# avr_programming_shield_Zif-Ken_reduced_b.net
KiCad netlist of a schematic drawn in EAGLE
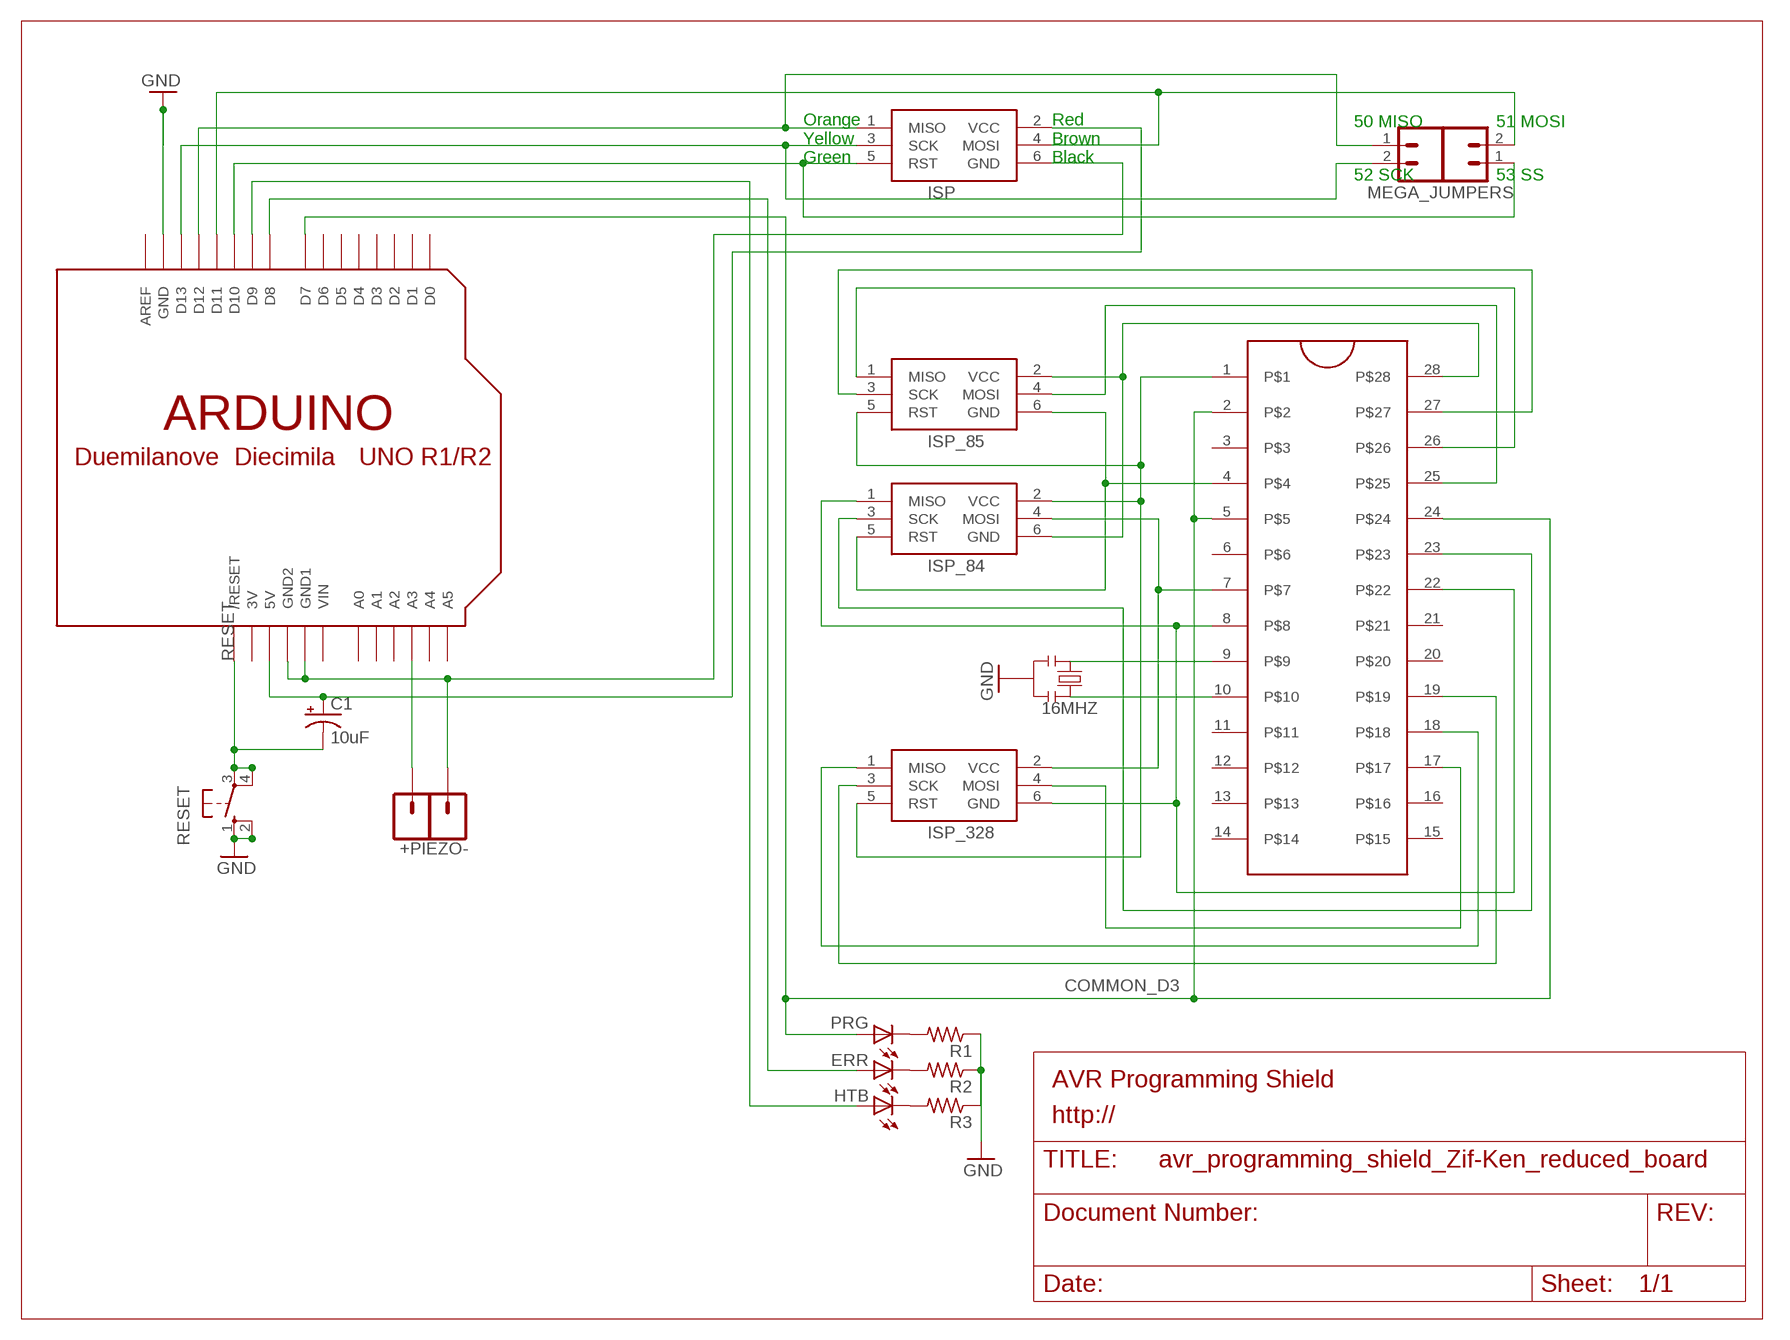
[diagram p0: schematic, sheet 1]

(export (version "E")
  (design (tool "Eeschema 10.0.6"))
  (components
    (comp (ref "+PIEZO-")
      (value "M01PTH")
      (footprint "eagle-import:1X01")
      (libsource (lib "eagle-import") (part "M01PTH"))
    )
    (comp (ref "16MHZ")
      (value "RESONATORPTH")
      (footprint "eagle-import:RESONATOR-PTH")
      (libsource (lib "eagle-import") (part "RESONATORPTH"))
    )
    (comp (ref "C1")
      (value "10uF")
      (footprint "eagle-import:CPOL-RADIAL-10UF-25V")
      (libsource (lib "eagle-import") (part "CAP_POLPTH2"))
    )
    (comp (ref "ERR")
      (value "LED3MM")
      (footprint "eagle-import:LED3MM")
      (libsource (lib "eagle-import") (part "LED3MM"))
    )
    (comp (ref "HTB")
      (value "LED3MM")
      (footprint "eagle-import:LED3MM")
      (libsource (lib "eagle-import") (part "LED3MM"))
    )
    (comp (ref "ISP")
      (value "AVRISP-6")
      (footprint "eagle-import:AVRISP")
      (libsource (lib "eagle-import") (part "AVRISP-6"))
    )
    (comp (ref "ISP_84")
      (value "AVRISP-6")
      (footprint "eagle-import:AVRISP")
      (libsource (lib "eagle-import") (part "AVRISP-6"))
    )
    (comp (ref "ISP_85")
      (value "AVRISP-6")
      (footprint "eagle-import:AVRISP")
      (libsource (lib "eagle-import") (part "AVRISP-6"))
    )
    (comp (ref "ISP_328")
      (value "AVRISP-6")
      (footprint "eagle-import:AVRISP")
      (libsource (lib "eagle-import") (part "AVRISP-6"))
    )
    (comp (ref "JP2")
      (value "M02PTH")
      (footprint "eagle-import:1X02")
      (libsource (lib "eagle-import") (part "M02PTH"))
    )
    (comp (ref "JP4")
      (value "M01PTH")
      (footprint "eagle-import:1X01")
      (libsource (lib "eagle-import") (part "M01PTH"))
    )
    (comp (ref "MEGA_JUMPERS")
      (value "M02PTH")
      (footprint "eagle-import:1X02")
      (libsource (lib "eagle-import") (part "M02PTH"))
    )
    (comp (ref "PRG")
      (value "LED3MM")
      (footprint "eagle-import:LED3MM")
      (libsource (lib "eagle-import") (part "LED3MM"))
    )
    (comp (ref "R1")
      (value "R-US_0204/2V")
      (footprint "eagle-import:0204V")
      (libsource (lib "eagle-import") (part "R-US_0204/2V"))
    )
    (comp (ref "R2")
      (value "R-US_0204/2V")
      (footprint "eagle-import:0204V")
      (libsource (lib "eagle-import") (part "R-US_0204/2V"))
    )
    (comp (ref "R3")
      (value "R-US_0204/2V")
      (footprint "eagle-import:0204V")
      (libsource (lib "eagle-import") (part "R-US_0204/2V"))
    )
    (comp (ref "RESET")
      (value "10-XX")
      (footprint "eagle-import:B3F-10XX")
      (fields (field (name "MPN") "B3F-1000"))
      (libsource (lib "eagle-import") (part "10-XX"))
    )
    (comp (ref "U$1")
      (value "ARDUINO-NOHOLE")
      (footprint "eagle-import:ARDUINO-NOHOLE")
      (libsource (lib "eagle-import") (part "ARDUINO-NOHOLE"))
    )
    (comp (ref "U$4")
      (value "ZIFSOCKET-28-3ZIFFSOCKET-28-3")
      (footprint "eagle-import:DIL28-3-ZIF_SOCKET")
      (libsource (lib "eagle-import") (part "ZIFSOCKET-28-3ZIFFSOCKET-28-3"))
    )
  )
  (nets
    (net (code "1") (name "/3V") (class "Default")
      (node (ref "U$1") (pin "3V") (pinfunction "3V_3V") (pintype "power_in"))
    )
    (net (code "2") (name "/COMMON_D3") (class "Default")
      (node (ref "PRG") (pin "A") (pinfunction "A_A") (pintype "passive"))
      (node (ref "U$1") (pin "D7") (pinfunction "D7_D7") (pintype "bidirectional"))
      (node (ref "U$4") (pin "2") (pinfunction "P$2_2") (pintype "bidirectional"))
      (node (ref "U$4") (pin "24") (pinfunction "P$24_24") (pintype "bidirectional"))
      (node (ref "U$4") (pin "5") (pinfunction "P$5_5") (pintype "bidirectional"))
    )
    (net (code "3") (name "/RESET") (class "Default")
      (node (ref "C1") (pin "2") (pinfunction "-_2") (pintype "passive"))
      (node (ref "RESET") (pin "3") (pinfunction "P_3") (pintype "passive"))
      (node (ref "RESET") (pin "4") (pinfunction "P1_4") (pintype "passive"))
      (node (ref "U$1") (pin "RESET") (pinfunction "/RESET_RESET") (pintype "bidirectional"))
    )
    (net (code "4") (name "/VIN") (class "Default")
      (node (ref "U$1") (pin "VIN") (pinfunction "VIN_VIN") (pintype "power_in"))
    )
    (net (code "5") (name "GND") (class "Default")
      (node (ref "+PIEZO-") (pin "1") (pinfunction "1_1") (pintype "passive"))
      (node (ref "16MHZ") (pin "2") (pinfunction "2_2") (pintype "passive"))
      (node (ref "ISP") (pin "6") (pinfunction "GND_6") (pintype "power_in"))
      (node (ref "R1") (pin "1") (pinfunction "1_1") (pintype "passive"))
      (node (ref "R2") (pin "1") (pinfunction "1_1") (pintype "passive"))
      (node (ref "R3") (pin "1") (pinfunction "1_1") (pintype "passive"))
      (node (ref "RESET") (pin "1") (pinfunction "S_1") (pintype "passive"))
      (node (ref "RESET") (pin "2") (pinfunction "S1_2") (pintype "passive"))
      (node (ref "U$1") (pin "GND") (pinfunction "GND_GND") (pintype "power_in"))
      (node (ref "U$1") (pin "GND1") (pinfunction "GND1_GND1") (pintype "power_in"))
      (node (ref "U$1") (pin "GND2") (pinfunction "GND2_GND2") (pintype "power_in"))
    )
    (net (code "6") (name "Net-(C1-+)") (class "Default")
      (node (ref "C1") (pin "1") (pinfunction "+_1") (pintype "passive"))
      (node (ref "ISP") (pin "2") (pinfunction "VCC_2") (pintype "power_in"))
      (node (ref "U$1") (pin "5V") (pinfunction "5V_5V") (pintype "power_in"))
    )
    (net (code "7") (name "Net-(ERR-C)") (class "Default")
      (node (ref "ERR") (pin "K") (pinfunction "C_K") (pintype "passive"))
      (node (ref "R2") (pin "2") (pinfunction "2_2") (pintype "passive"))
    )
    (net (code "8") (name "Net-(ERR-PadA)") (class "Default")
      (node (ref "ERR") (pin "A") (pinfunction "A_A") (pintype "passive"))
      (node (ref "U$1") (pin "D8") (pinfunction "D8_D8") (pintype "bidirectional"))
    )
    (net (code "9") (name "Net-(HTB-C)") (class "Default")
      (node (ref "HTB") (pin "K") (pinfunction "C_K") (pintype "passive"))
      (node (ref "R3") (pin "2") (pinfunction "2_2") (pintype "passive"))
    )
    (net (code "10") (name "Net-(HTB-PadA)") (class "Default")
      (node (ref "HTB") (pin "A") (pinfunction "A_A") (pintype "passive"))
      (node (ref "U$1") (pin "D9") (pinfunction "D9_D9") (pintype "bidirectional"))
    )
    (net (code "11") (name "Net-(ISP-MISO)") (class "Default")
      (node (ref "ISP") (pin "1") (pinfunction "MISO_1") (pintype "input"))
      (node (ref "MEGA_JUMPERS") (pin "1") (pinfunction "1_1") (pintype "passive"))
      (node (ref "U$1") (pin "D12") (pinfunction "D12_D12") (pintype "bidirectional"))
    )
    (net (code "12") (name "Net-(ISP-MOSI)") (class "Default")
      (node (ref "ISP") (pin "4") (pinfunction "MOSI_4") (pintype "output"))
      (node (ref "JP2") (pin "2") (pinfunction "2_2") (pintype "passive"))
      (node (ref "U$1") (pin "D11") (pinfunction "D11_D11") (pintype "bidirectional"))
    )
    (net (code "13") (name "Net-(ISP-RST)") (class "Default")
      (node (ref "ISP") (pin "5") (pinfunction "RST_5") (pintype "output"))
      (node (ref "JP2") (pin "1") (pinfunction "1_1") (pintype "passive"))
      (node (ref "U$1") (pin "D10") (pinfunction "D10_D10") (pintype "bidirectional"))
    )
    (net (code "14") (name "Net-(ISP-SCK)") (class "Default")
      (node (ref "ISP") (pin "3") (pinfunction "SCK_3") (pintype "output"))
      (node (ref "MEGA_JUMPERS") (pin "2") (pinfunction "2_2") (pintype "passive"))
      (node (ref "U$1") (pin "D13") (pinfunction "D13_D13") (pintype "bidirectional"))
    )
    (net (code "15") (name "Net-(ISP_84-GND)") (class "Default")
      (node (ref "ISP_84") (pin "6") (pinfunction "GND_6") (pintype "power_in"))
      (node (ref "ISP_85") (pin "2") (pinfunction "VCC_2") (pintype "power_in"))
      (node (ref "U$4") (pin "28") (pinfunction "P$28_28") (pintype "bidirectional"))
    )
    (net (code "16") (name "Net-(ISP_84-RST)") (class "Default")
      (node (ref "ISP_84") (pin "5") (pinfunction "RST_5") (pintype "output"))
      (node (ref "ISP_85") (pin "6") (pinfunction "GND_6") (pintype "power_in"))
      (node (ref "U$4") (pin "4") (pinfunction "P$4_4") (pintype "bidirectional"))
    )
    (net (code "17") (name "Net-(ISP_84-SCK)") (class "Default")
      (node (ref "ISP_84") (pin "3") (pinfunction "SCK_3") (pintype "output"))
      (node (ref "U$4") (pin "23") (pinfunction "P$23_23") (pintype "bidirectional"))
    )
    (net (code "18") (name "Net-(ISP_85-MISO)") (class "Default")
      (node (ref "ISP_85") (pin "1") (pinfunction "MISO_1") (pintype "input"))
      (node (ref "U$4") (pin "26") (pinfunction "P$26_26") (pintype "bidirectional"))
    )
    (net (code "19") (name "Net-(ISP_85-MOSI)") (class "Default")
      (node (ref "ISP_85") (pin "4") (pinfunction "MOSI_4") (pintype "output"))
      (node (ref "U$4") (pin "25") (pinfunction "P$25_25") (pintype "bidirectional"))
    )
    (net (code "20") (name "Net-(ISP_85-SCK)") (class "Default")
      (node (ref "ISP_85") (pin "3") (pinfunction "SCK_3") (pintype "output"))
      (node (ref "U$4") (pin "27") (pinfunction "P$27_27") (pintype "bidirectional"))
    )
    (net (code "21") (name "Net-(ISP_328-GND)") (class "Default")
      (node (ref "ISP_328") (pin "6") (pinfunction "GND_6") (pintype "power_in"))
      (node (ref "ISP_84") (pin "1") (pinfunction "MISO_1") (pintype "input"))
      (node (ref "U$4") (pin "22") (pinfunction "P$22_22") (pintype "bidirectional"))
      (node (ref "U$4") (pin "8") (pinfunction "P$8_8") (pintype "bidirectional"))
    )
    (net (code "22") (name "Net-(ISP_328-MISO)") (class "Default")
      (node (ref "ISP_328") (pin "1") (pinfunction "MISO_1") (pintype "input"))
      (node (ref "U$4") (pin "18") (pinfunction "P$18_18") (pintype "bidirectional"))
    )
    (net (code "23") (name "Net-(ISP_328-MOSI)") (class "Default")
      (node (ref "ISP_328") (pin "4") (pinfunction "MOSI_4") (pintype "output"))
      (node (ref "U$4") (pin "17") (pinfunction "P$17_17") (pintype "bidirectional"))
    )
    (net (code "24") (name "Net-(ISP_328-RST)") (class "Default")
      (node (ref "ISP_328") (pin "5") (pinfunction "RST_5") (pintype "output"))
      (node (ref "ISP_84") (pin "2") (pinfunction "VCC_2") (pintype "power_in"))
      (node (ref "ISP_85") (pin "5") (pinfunction "RST_5") (pintype "output"))
      (node (ref "U$4") (pin "1") (pinfunction "P$1_1") (pintype "bidirectional"))
    )
    (net (code "25") (name "Net-(ISP_328-SCK)") (class "Default")
      (node (ref "ISP_328") (pin "3") (pinfunction "SCK_3") (pintype "output"))
      (node (ref "U$4") (pin "19") (pinfunction "P$19_19") (pintype "bidirectional"))
    )
    (net (code "26") (name "Net-(ISP_328-VCC)") (class "Default")
      (node (ref "ISP_328") (pin "2") (pinfunction "VCC_2") (pintype "power_in"))
      (node (ref "ISP_84") (pin "4") (pinfunction "MOSI_4") (pintype "output"))
      (node (ref "U$4") (pin "7") (pinfunction "P$7_7") (pintype "bidirectional"))
    )
    (net (code "27") (name "Net-(JP4-Pad1)") (class "Default")
      (node (ref "JP4") (pin "1") (pinfunction "1_1") (pintype "passive"))
      (node (ref "U$1") (pin "A3") (pinfunction "A3_A3") (pintype "bidirectional"))
    )
    (net (code "28") (name "Net-(PRG-C)") (class "Default")
      (node (ref "PRG") (pin "K") (pinfunction "C_K") (pintype "passive"))
      (node (ref "R1") (pin "2") (pinfunction "2_2") (pintype "passive"))
    )
    (net (code "29") (name "Net-(U$4-P$9)") (class "Default")
      (node (ref "16MHZ") (pin "1") (pinfunction "1_1") (pintype "passive"))
      (node (ref "U$4") (pin "9") (pinfunction "P$9_9") (pintype "bidirectional"))
    )
    (net (code "30") (name "Net-(U$4-P$10)") (class "Default")
      (node (ref "16MHZ") (pin "3") (pinfunction "3_3") (pintype "passive"))
      (node (ref "U$4") (pin "10") (pinfunction "P$10_10") (pintype "bidirectional"))
    )
    (net (code "31") (name "unconnected-(U$1-PadA0)") (class "Default")
      (node (ref "U$1") (pin "A0") (pinfunction "A0_A0") (pintype "bidirectional"))
    )
    (net (code "32") (name "unconnected-(U$1-PadA1)") (class "Default")
      (node (ref "U$1") (pin "A1") (pinfunction "A1_A1") (pintype "bidirectional"))
    )
    (net (code "33") (name "unconnected-(U$1-PadA2)") (class "Default")
      (node (ref "U$1") (pin "A2") (pinfunction "A2_A2") (pintype "bidirectional"))
    )
    (net (code "34") (name "unconnected-(U$1-PadA4)") (class "Default")
      (node (ref "U$1") (pin "A4") (pinfunction "A4_A4") (pintype "bidirectional"))
    )
    (net (code "35") (name "unconnected-(U$1-PadA5)") (class "Default")
      (node (ref "U$1") (pin "A5") (pinfunction "A5_A5") (pintype "bidirectional"))
    )
    (net (code "36") (name "unconnected-(U$1-PadAREF)") (class "Default")
      (node (ref "U$1") (pin "AREF") (pinfunction "AREF_AREF") (pintype "bidirectional"))
    )
    (net (code "37") (name "unconnected-(U$1-PadD0)") (class "Default")
      (node (ref "U$1") (pin "D0") (pinfunction "D0_D0") (pintype "bidirectional"))
    )
    (net (code "38") (name "unconnected-(U$1-PadD1)") (class "Default")
      (node (ref "U$1") (pin "D1") (pinfunction "D1_D1") (pintype "bidirectional"))
    )
    (net (code "39") (name "unconnected-(U$1-PadD2)") (class "Default")
      (node (ref "U$1") (pin "D2") (pinfunction "D2_D2") (pintype "bidirectional"))
    )
    (net (code "40") (name "unconnected-(U$1-PadD3)") (class "Default")
      (node (ref "U$1") (pin "D3") (pinfunction "D3_D3") (pintype "bidirectional"))
    )
    (net (code "41") (name "unconnected-(U$1-PadD4)") (class "Default")
      (node (ref "U$1") (pin "D4") (pinfunction "D4_D4") (pintype "bidirectional"))
    )
    (net (code "42") (name "unconnected-(U$1-PadD5)") (class "Default")
      (node (ref "U$1") (pin "D5") (pinfunction "D5_D5") (pintype "bidirectional"))
    )
    (net (code "43") (name "unconnected-(U$1-PadD6)") (class "Default")
      (node (ref "U$1") (pin "D6") (pinfunction "D6_D6") (pintype "bidirectional"))
    )
    (net (code "44") (name "unconnected-(U$4-P$3-Pad3)") (class "Default")
      (node (ref "U$4") (pin "3") (pinfunction "P$3_3") (pintype "bidirectional"))
    )
    (net (code "45") (name "unconnected-(U$4-P$6-Pad6)") (class "Default")
      (node (ref "U$4") (pin "6") (pinfunction "P$6_6") (pintype "bidirectional"))
    )
    (net (code "46") (name "unconnected-(U$4-P$11-Pad11)") (class "Default")
      (node (ref "U$4") (pin "11") (pinfunction "P$11_11") (pintype "bidirectional"))
    )
    (net (code "47") (name "unconnected-(U$4-P$12-Pad12)") (class "Default")
      (node (ref "U$4") (pin "12") (pinfunction "P$12_12") (pintype "bidirectional"))
    )
    (net (code "48") (name "unconnected-(U$4-P$13-Pad13)") (class "Default")
      (node (ref "U$4") (pin "13") (pinfunction "P$13_13") (pintype "bidirectional"))
    )
    (net (code "49") (name "unconnected-(U$4-P$14-Pad14)") (class "Default")
      (node (ref "U$4") (pin "14") (pinfunction "P$14_14") (pintype "bidirectional"))
    )
    (net (code "50") (name "unconnected-(U$4-P$15-Pad15)") (class "Default")
      (node (ref "U$4") (pin "15") (pinfunction "P$15_15") (pintype "bidirectional"))
    )
    (net (code "51") (name "unconnected-(U$4-P$16-Pad16)") (class "Default")
      (node (ref "U$4") (pin "16") (pinfunction "P$16_16") (pintype "bidirectional"))
    )
    (net (code "52") (name "unconnected-(U$4-P$20-Pad20)") (class "Default")
      (node (ref "U$4") (pin "20") (pinfunction "P$20_20") (pintype "bidirectional"))
    )
    (net (code "53") (name "unconnected-(U$4-P$21-Pad21)") (class "Default")
      (node (ref "U$4") (pin "21") (pinfunction "P$21_21") (pintype "bidirectional"))
    )
  )
)
